# Connectors.net
KiCad netlist of a schematic drawn in Altium Designer
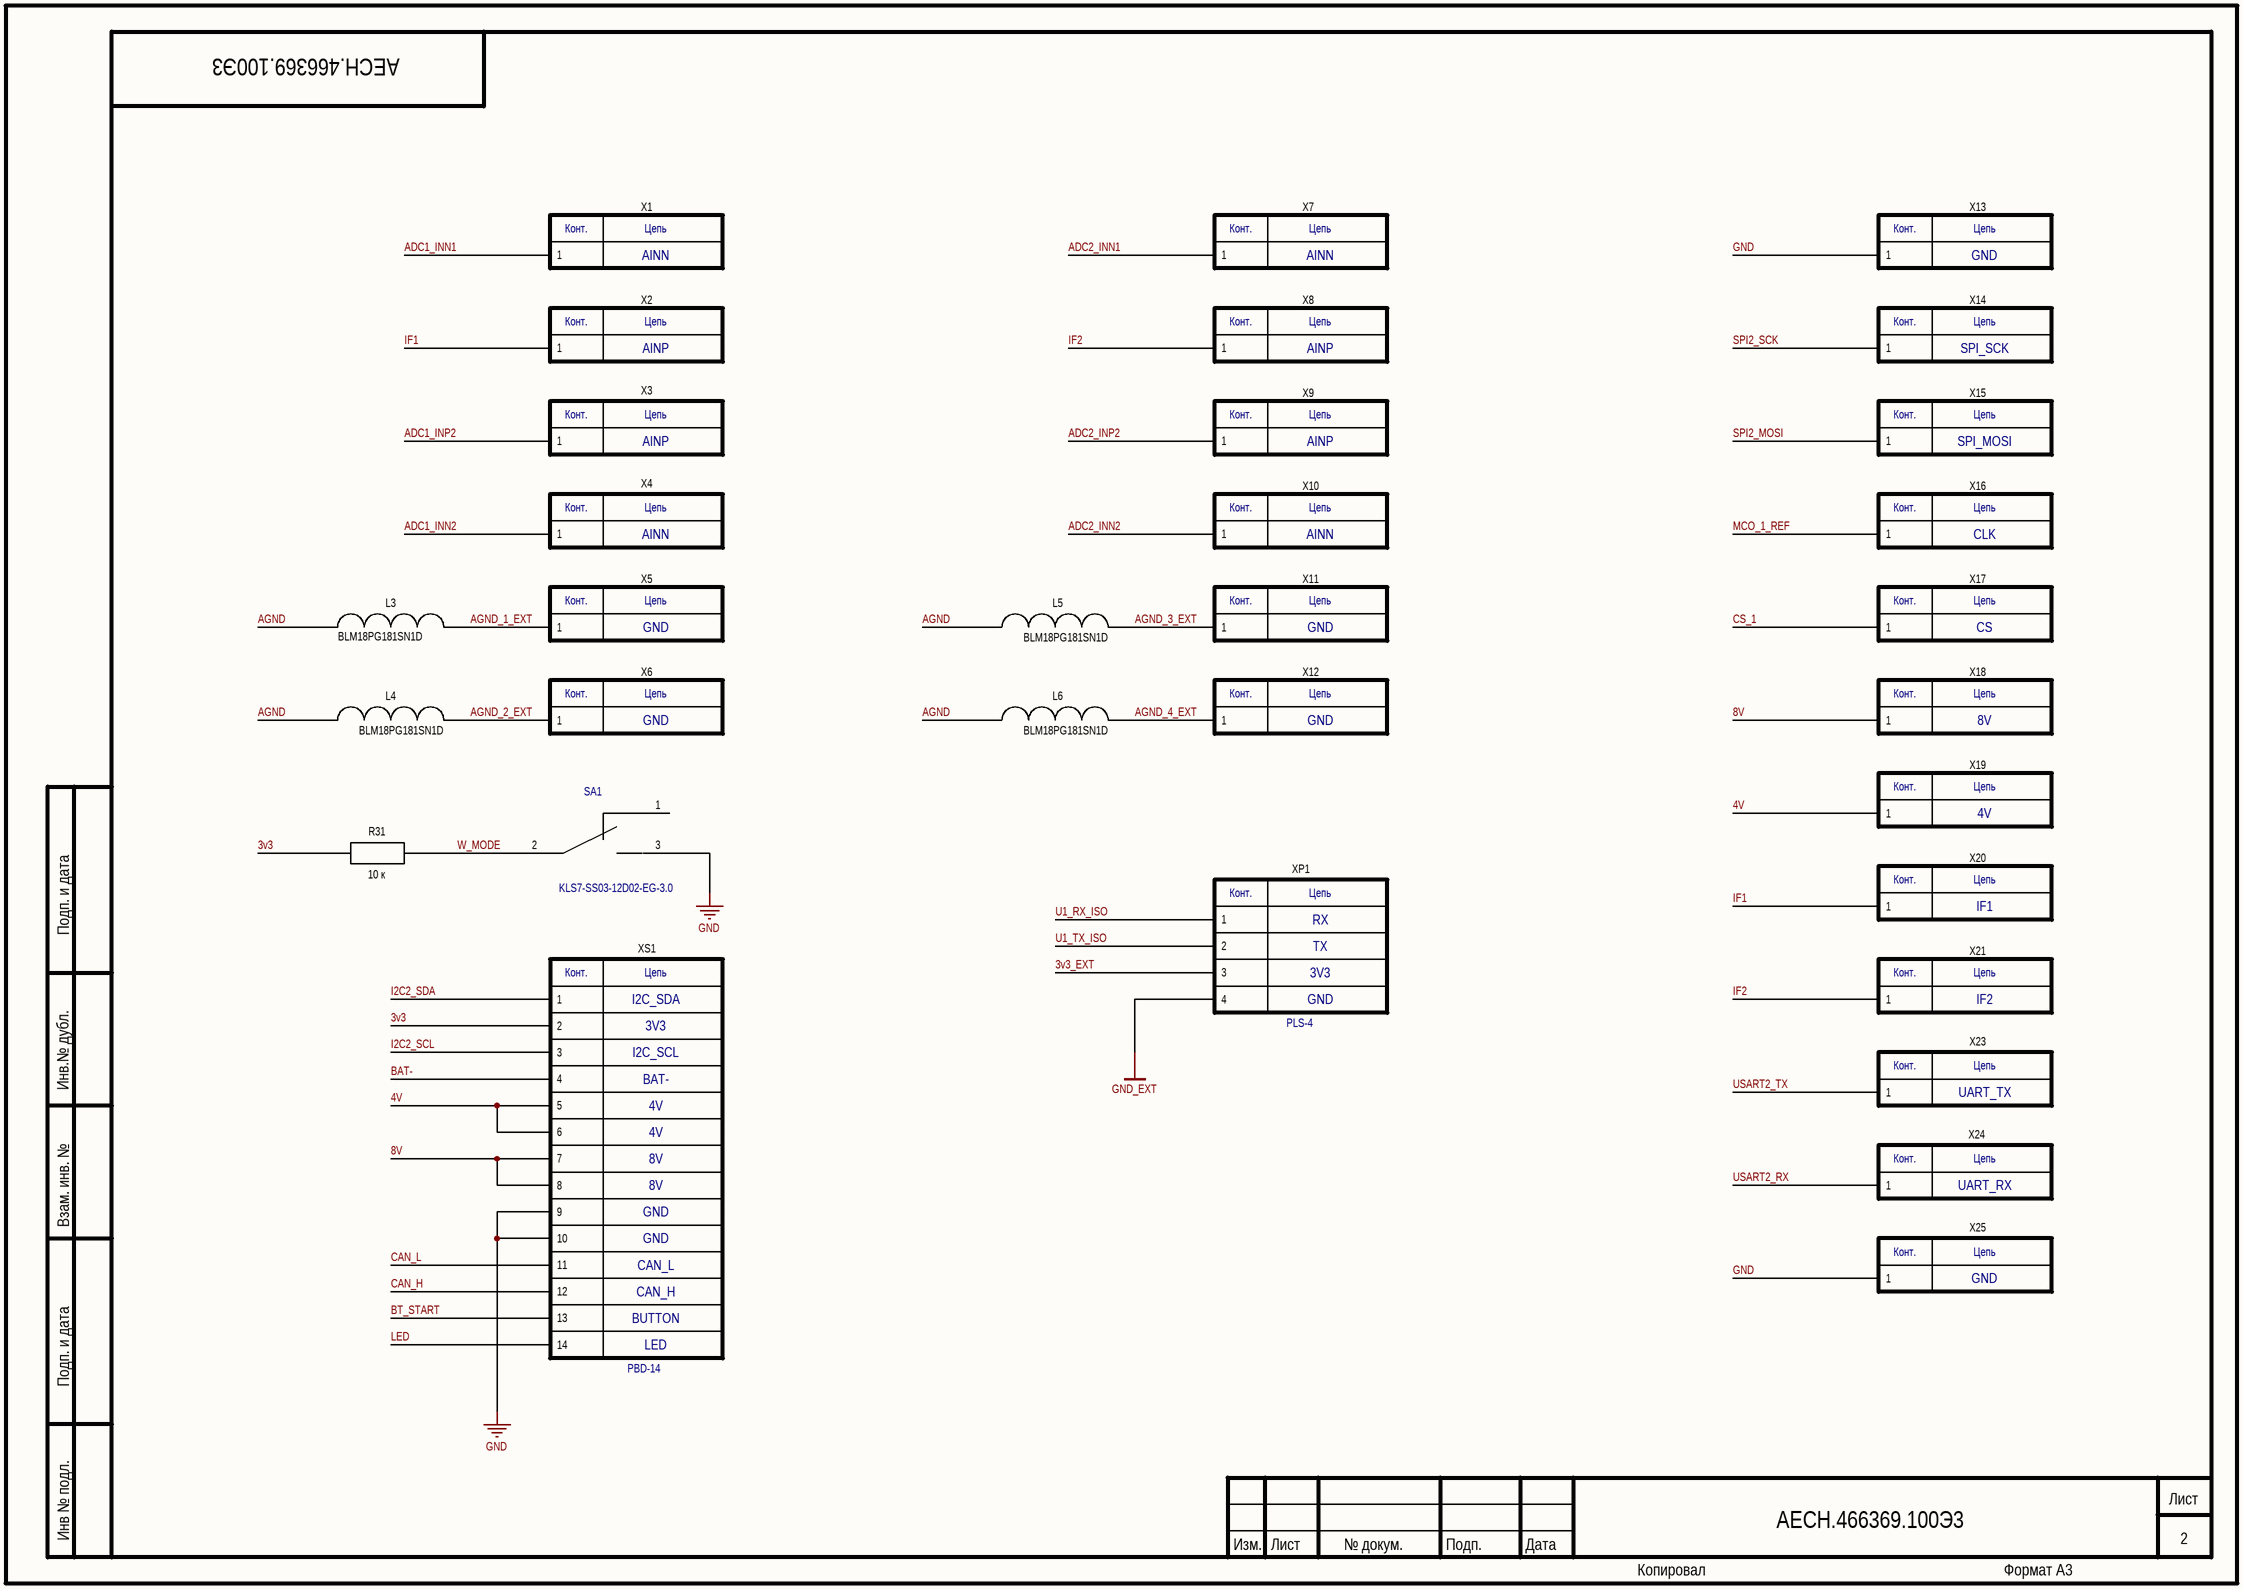
[diagram p0: Connectors.SchDoc]

(export (version "E")
  (design (tool "Eeschema 10.0.6"))
  (components
    (comp (ref "L3") (value "BLM18PG181SN1D") (footprint "INDC_0603") (libsource (lib "5ko") (part "L_1")))
    (comp (ref "L4") (value "BLM18PG181SN1D") (footprint "INDC_0603") (libsource (lib "5ko") (part "L_1")))
    (comp (ref "L5") (value "BLM18PG181SN1D") (footprint "INDC_0603") (libsource (lib "5ko") (part "L_1")))
    (comp (ref "L6") (value "BLM18PG181SN1D") (footprint "INDC_0603") (libsource (lib "5ko") (part "L_1")))
    (comp (ref "R31")
      (value "10 к")
      (footprint "R0603")
      (fields
        (field (name "TOLERANCE") "±5%")
        (field (name "POWER") "0.1 Вт")
        (field (name "PARTNUMBER") "RC0603JR-0710KL")
      )
      (libsource (lib "5ko") (part "R"))
    )
    (comp (ref "SA1")
      (value "Switch")
      (footprint "KLS7-SS03-12D02")
      (fields (field (name "PARTNUMBER") "KLS7-SS03-12D02-EG-3.0"))
      (libsource (lib "5ko") (part "Switch"))
    )
    (comp (ref "X1") (value "1pin") (footprint "lam 4x2") (libsource (lib "5ko") (part "1pin")))
    (comp (ref "X2") (value "1pin") (footprint "lam 4x2") (libsource (lib "5ko") (part "1pin")))
    (comp (ref "X3") (value "1pin") (footprint "lam 4x2") (libsource (lib "5ko") (part "1pin")))
    (comp (ref "X4") (value "1pin") (footprint "lam 4x2") (libsource (lib "5ko") (part "1pin")))
    (comp (ref "X5") (value "1pin") (footprint "lam 4x2") (libsource (lib "5ko") (part "1pin")))
    (comp (ref "X6") (value "1pin") (footprint "lam 4x2") (libsource (lib "5ko") (part "1pin")))
    (comp (ref "X7") (value "1pin") (footprint "lam 4x2") (libsource (lib "5ko") (part "1pin")))
    (comp (ref "X8") (value "1pin") (footprint "lam 4x2") (libsource (lib "5ko") (part "1pin")))
    (comp (ref "X9") (value "1pin") (footprint "lam 4x2") (libsource (lib "5ko") (part "1pin")))
    (comp (ref "X10") (value "1pin") (footprint "lam 4x2") (libsource (lib "5ko") (part "1pin")))
    (comp (ref "X11") (value "1pin") (footprint "lam 4x2") (libsource (lib "5ko") (part "1pin")))
    (comp (ref "X12") (value "1pin") (footprint "lam 4x2") (libsource (lib "5ko") (part "1pin")))
    (comp (ref "X13") (value "1pin") (footprint "lam 4x2") (libsource (lib "5ko") (part "1pin")))
    (comp (ref "X14") (value "1pin") (footprint "lam 4x2") (libsource (lib "5ko") (part "1pin")))
    (comp (ref "X15") (value "1pin") (footprint "lam 4x2") (libsource (lib "5ko") (part "1pin")))
    (comp (ref "X16") (value "1pin") (footprint "lam 4x2") (libsource (lib "5ko") (part "1pin")))
    (comp (ref "X17") (value "1pin") (footprint "lam 4x2") (libsource (lib "5ko") (part "1pin")))
    (comp (ref "X18") (value "1pin") (footprint "lam 4x2") (libsource (lib "5ko") (part "1pin")))
    (comp (ref "X19") (value "1pin") (footprint "lam 4x2") (libsource (lib "5ko") (part "1pin")))
    (comp (ref "X20") (value "1pin") (footprint "lam 4x2") (libsource (lib "5ko") (part "1pin")))
    (comp (ref "X21") (value "1pin") (footprint "lam 4x2") (libsource (lib "5ko") (part "1pin")))
    (comp (ref "X23") (value "1pin") (footprint "lam 4x2") (libsource (lib "5ko") (part "1pin")))
    (comp (ref "X24") (value "1pin") (footprint "lam 4x2") (libsource (lib "5ko") (part "1pin")))
    (comp (ref "X25") (value "1pin") (footprint "lam 4x2") (libsource (lib "5ko") (part "1pin")))
    (comp (ref "XP1")
      (value "4pin")
      (footprint "PLS-4")
      (fields (field (name "PARTNUMBER") "PLS-4"))
      (libsource (lib "5ko") (part "4pin"))
    )
    (comp (ref "XS1")
      (value "14pin")
      (footprint "PBD-14")
      (fields (field (name "PARTNUMBER") "PBD-14"))
      (libsource (lib "5ko") (part "14pin"))
    )
  )
  (nets
    (net (code "1") (name "/3v3") (class "Default")
      (node (ref "R31") (pin "1") (pinfunction "1_1") (pintype "passive"))
      (node (ref "XS1") (pin "2") (pinfunction "2_2") (pintype "passive"))
    )
    (net (code "2") (name "/3v3_EXT") (class "Default")
      (node (ref "XP1") (pin "3") (pinfunction "3_3") (pintype "passive"))
    )
    (net (code "3") (name "/4V") (class "Default")
      (node (ref "X19") (pin "1") (pinfunction "1_1") (pintype "passive"))
      (node (ref "XS1") (pin "5") (pinfunction "5_5") (pintype "passive"))
      (node (ref "XS1") (pin "6") (pinfunction "6_6") (pintype "passive"))
    )
    (net (code "4") (name "/8V") (class "Default")
      (node (ref "X18") (pin "1") (pinfunction "1_1") (pintype "passive"))
      (node (ref "XS1") (pin "7") (pinfunction "7_7") (pintype "passive"))
      (node (ref "XS1") (pin "8") (pinfunction "8_8") (pintype "passive"))
    )
    (net (code "5") (name "/ADC1_INN1") (class "Default")
      (node (ref "X1") (pin "1") (pinfunction "1_1") (pintype "passive"))
    )
    (net (code "6") (name "/ADC1_INN2") (class "Default")
      (node (ref "X4") (pin "1") (pinfunction "1_1") (pintype "passive"))
    )
    (net (code "7") (name "/ADC1_INP2") (class "Default")
      (node (ref "X3") (pin "1") (pinfunction "1_1") (pintype "passive"))
    )
    (net (code "8") (name "/ADC2_INN1") (class "Default")
      (node (ref "X7") (pin "1") (pinfunction "1_1") (pintype "passive"))
    )
    (net (code "9") (name "/ADC2_INN2") (class "Default")
      (node (ref "X10") (pin "1") (pinfunction "1_1") (pintype "passive"))
    )
    (net (code "10") (name "/ADC2_INP2") (class "Default")
      (node (ref "X9") (pin "1") (pinfunction "1_1") (pintype "passive"))
    )
    (net (code "11") (name "/AGND") (class "Default")
      (node (ref "L3") (pin "2") (pinfunction "2_2") (pintype "passive"))
      (node (ref "L4") (pin "2") (pinfunction "2_2") (pintype "passive"))
      (node (ref "L5") (pin "2") (pinfunction "2_2") (pintype "passive"))
      (node (ref "L6") (pin "2") (pinfunction "2_2") (pintype "passive"))
    )
    (net (code "12") (name "/AGND_1_EXT") (class "Default")
      (node (ref "L3") (pin "1") (pinfunction "1_1") (pintype "passive"))
      (node (ref "X5") (pin "1") (pinfunction "1_1") (pintype "passive"))
    )
    (net (code "13") (name "/AGND_2_EXT") (class "Default")
      (node (ref "L4") (pin "1") (pinfunction "1_1") (pintype "passive"))
      (node (ref "X6") (pin "1") (pinfunction "1_1") (pintype "passive"))
    )
    (net (code "14") (name "/AGND_3_EXT") (class "Default")
      (node (ref "L5") (pin "1") (pinfunction "1_1") (pintype "passive"))
      (node (ref "X11") (pin "1") (pinfunction "1_1") (pintype "passive"))
    )
    (net (code "15") (name "/AGND_4_EXT") (class "Default")
      (node (ref "L6") (pin "1") (pinfunction "1_1") (pintype "passive"))
      (node (ref "X12") (pin "1") (pinfunction "1_1") (pintype "passive"))
    )
    (net (code "16") (name "/BAT-") (class "Default")
      (node (ref "XS1") (pin "4") (pinfunction "4_4") (pintype "passive"))
    )
    (net (code "17") (name "/BT_START") (class "Default")
      (node (ref "XS1") (pin "13") (pinfunction "13_13") (pintype "passive"))
    )
    (net (code "18") (name "/CAN_H") (class "Default")
      (node (ref "XS1") (pin "12") (pinfunction "12_12") (pintype "passive"))
    )
    (net (code "19") (name "/CAN_L") (class "Default")
      (node (ref "XS1") (pin "11") (pinfunction "11_11") (pintype "passive"))
    )
    (net (code "20") (name "/CS_1") (class "Default")
      (node (ref "X17") (pin "1") (pinfunction "1_1") (pintype "passive"))
    )
    (net (code "21") (name "/I2C2_SCL") (class "Default")
      (node (ref "XS1") (pin "3") (pinfunction "3_3") (pintype "passive"))
    )
    (net (code "22") (name "/I2C2_SDA") (class "Default")
      (node (ref "XS1") (pin "1") (pinfunction "1_1") (pintype "passive"))
    )
    (net (code "23") (name "/IF1") (class "Default")
      (node (ref "X2") (pin "1") (pinfunction "1_1") (pintype "passive"))
      (node (ref "X20") (pin "1") (pinfunction "1_1") (pintype "passive"))
    )
    (net (code "24") (name "/IF2") (class "Default")
      (node (ref "X21") (pin "1") (pinfunction "1_1") (pintype "passive"))
      (node (ref "X8") (pin "1") (pinfunction "1_1") (pintype "passive"))
    )
    (net (code "25") (name "/LED") (class "Default")
      (node (ref "XS1") (pin "14") (pinfunction "14_14") (pintype "passive"))
    )
    (net (code "26") (name "/MCO_1_REF") (class "Default")
      (node (ref "X16") (pin "1") (pinfunction "1_1") (pintype "passive"))
    )
    (net (code "27") (name "/SPI2_MOSI") (class "Default")
      (node (ref "X15") (pin "1") (pinfunction "1_1") (pintype "passive"))
    )
    (net (code "28") (name "/SPI2_SCK") (class "Default")
      (node (ref "X14") (pin "1") (pinfunction "1_1") (pintype "passive"))
    )
    (net (code "29") (name "/U1_RX_ISO") (class "Default")
      (node (ref "XP1") (pin "1") (pinfunction "1_1") (pintype "passive"))
    )
    (net (code "30") (name "/U1_TX_ISO") (class "Default")
      (node (ref "XP1") (pin "2") (pinfunction "2_2") (pintype "passive"))
    )
    (net (code "31") (name "/USART2_RX") (class "Default")
      (node (ref "X24") (pin "1") (pinfunction "1_1") (pintype "passive"))
    )
    (net (code "32") (name "/USART2_TX") (class "Default")
      (node (ref "X23") (pin "1") (pinfunction "1_1") (pintype "passive"))
    )
    (net (code "33") (name "/W_MODE") (class "Default")
      (node (ref "R31") (pin "2") (pinfunction "2_2") (pintype "passive"))
      (node (ref "SA1") (pin "2") (pintype "passive"))
    )
    (net (code "34") (name "GND") (class "Default")
      (node (ref "SA1") (pin "3") (pintype "passive"))
      (node (ref "X13") (pin "1") (pinfunction "1_1") (pintype "passive"))
      (node (ref "X25") (pin "1") (pinfunction "1_1") (pintype "passive"))
      (node (ref "XS1") (pin "10") (pinfunction "10_10") (pintype "passive"))
      (node (ref "XS1") (pin "9") (pinfunction "9_9") (pintype "passive"))
    )
    (net (code "35") (name "GND_EXT") (class "Default")
      (node (ref "XP1") (pin "4") (pinfunction "4_4") (pintype "passive"))
    )
    (net (code "36") (name "unconnected-(SA1-Pad1)") (class "Default")
      (node (ref "SA1") (pin "1") (pintype "passive"))
    )
  )
)
